# D3R900.net
KiCad netlist of a schematic drawn in Altium Designer
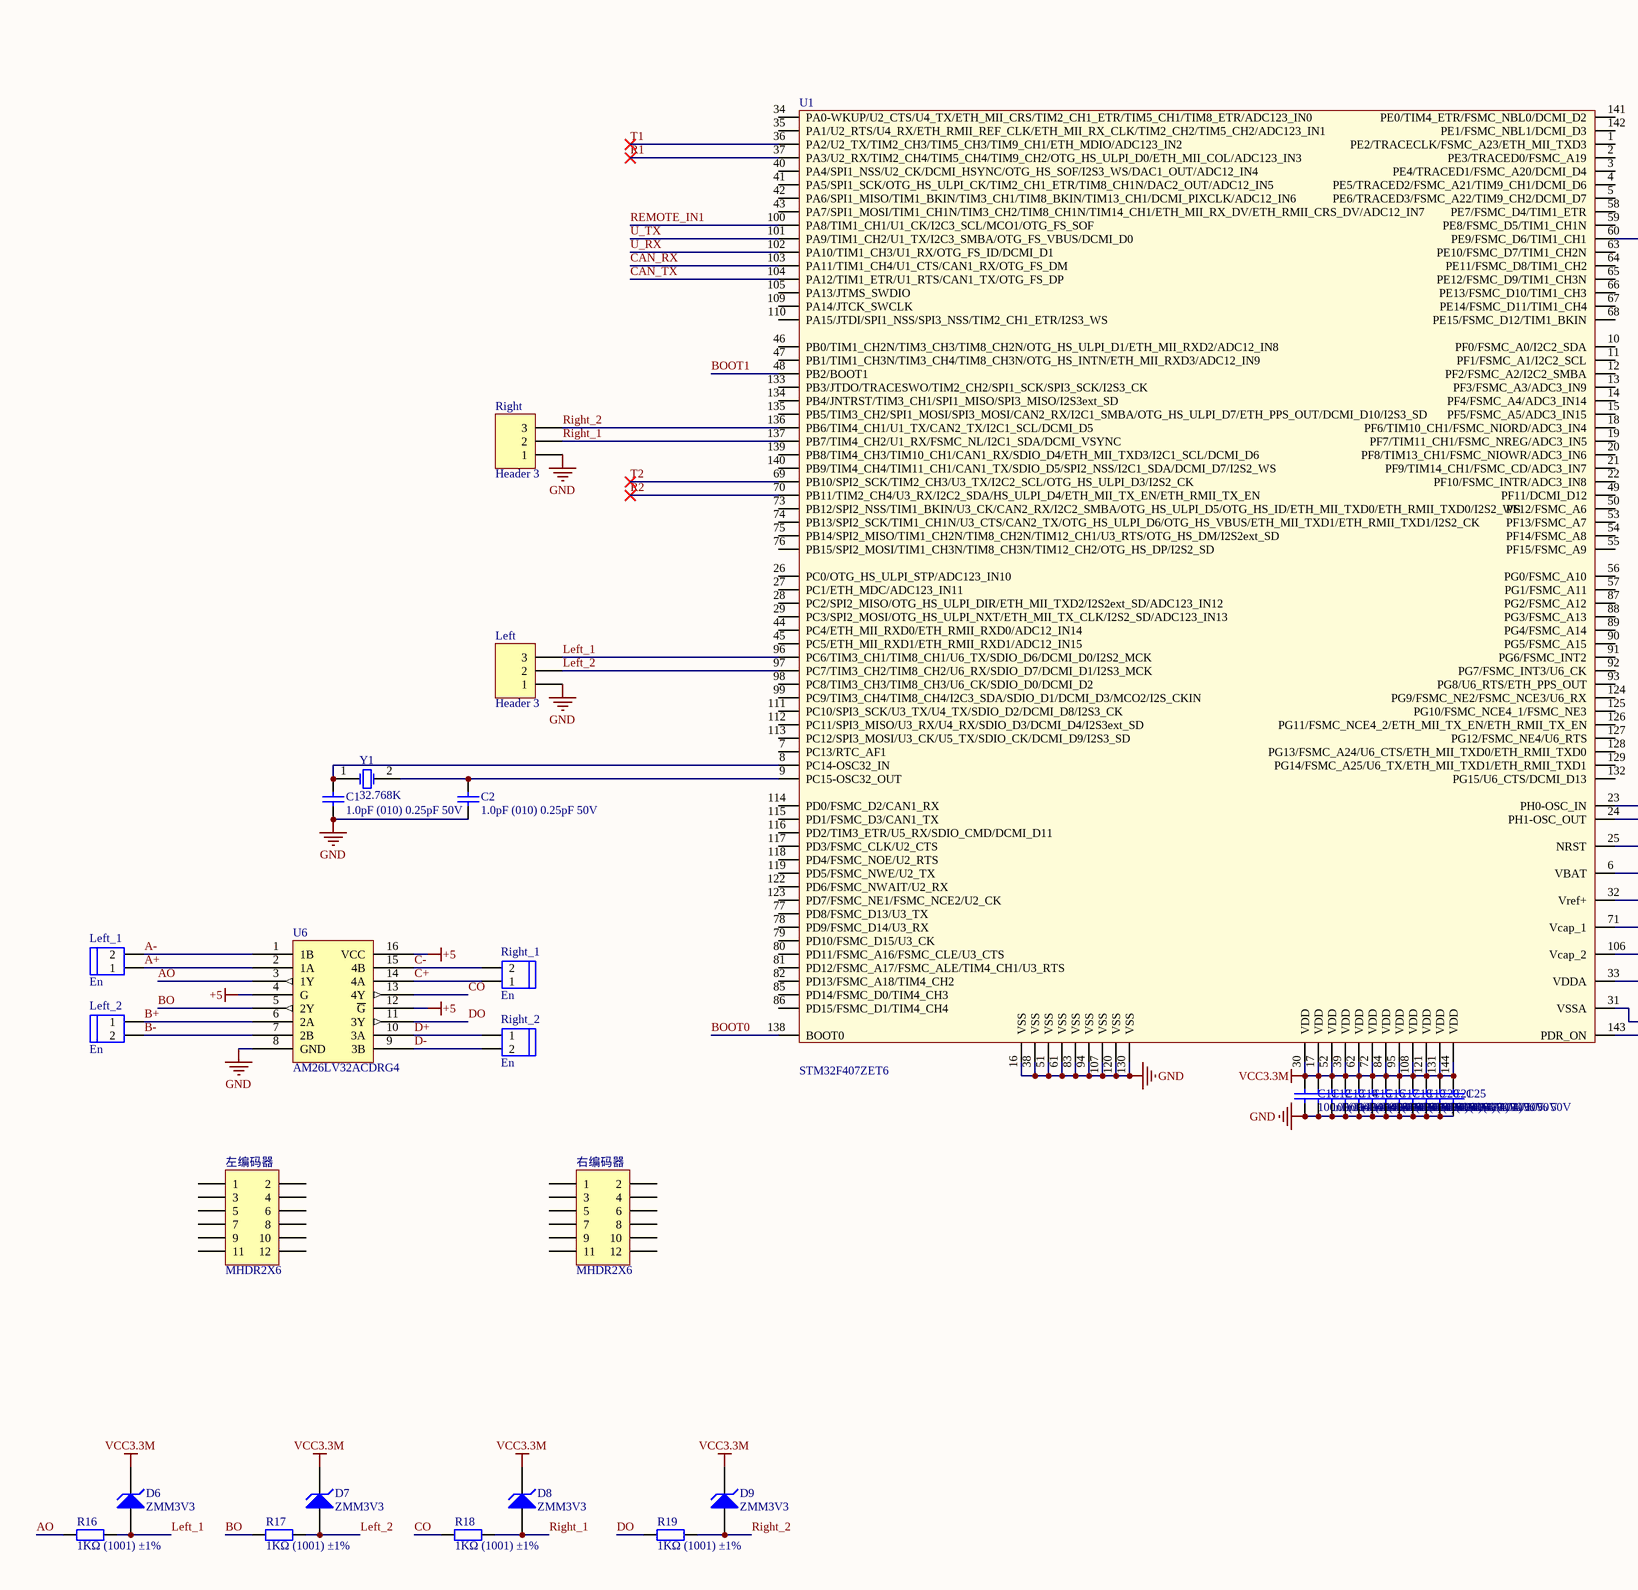
[diagram p0: D3R900.SchDoc, left]
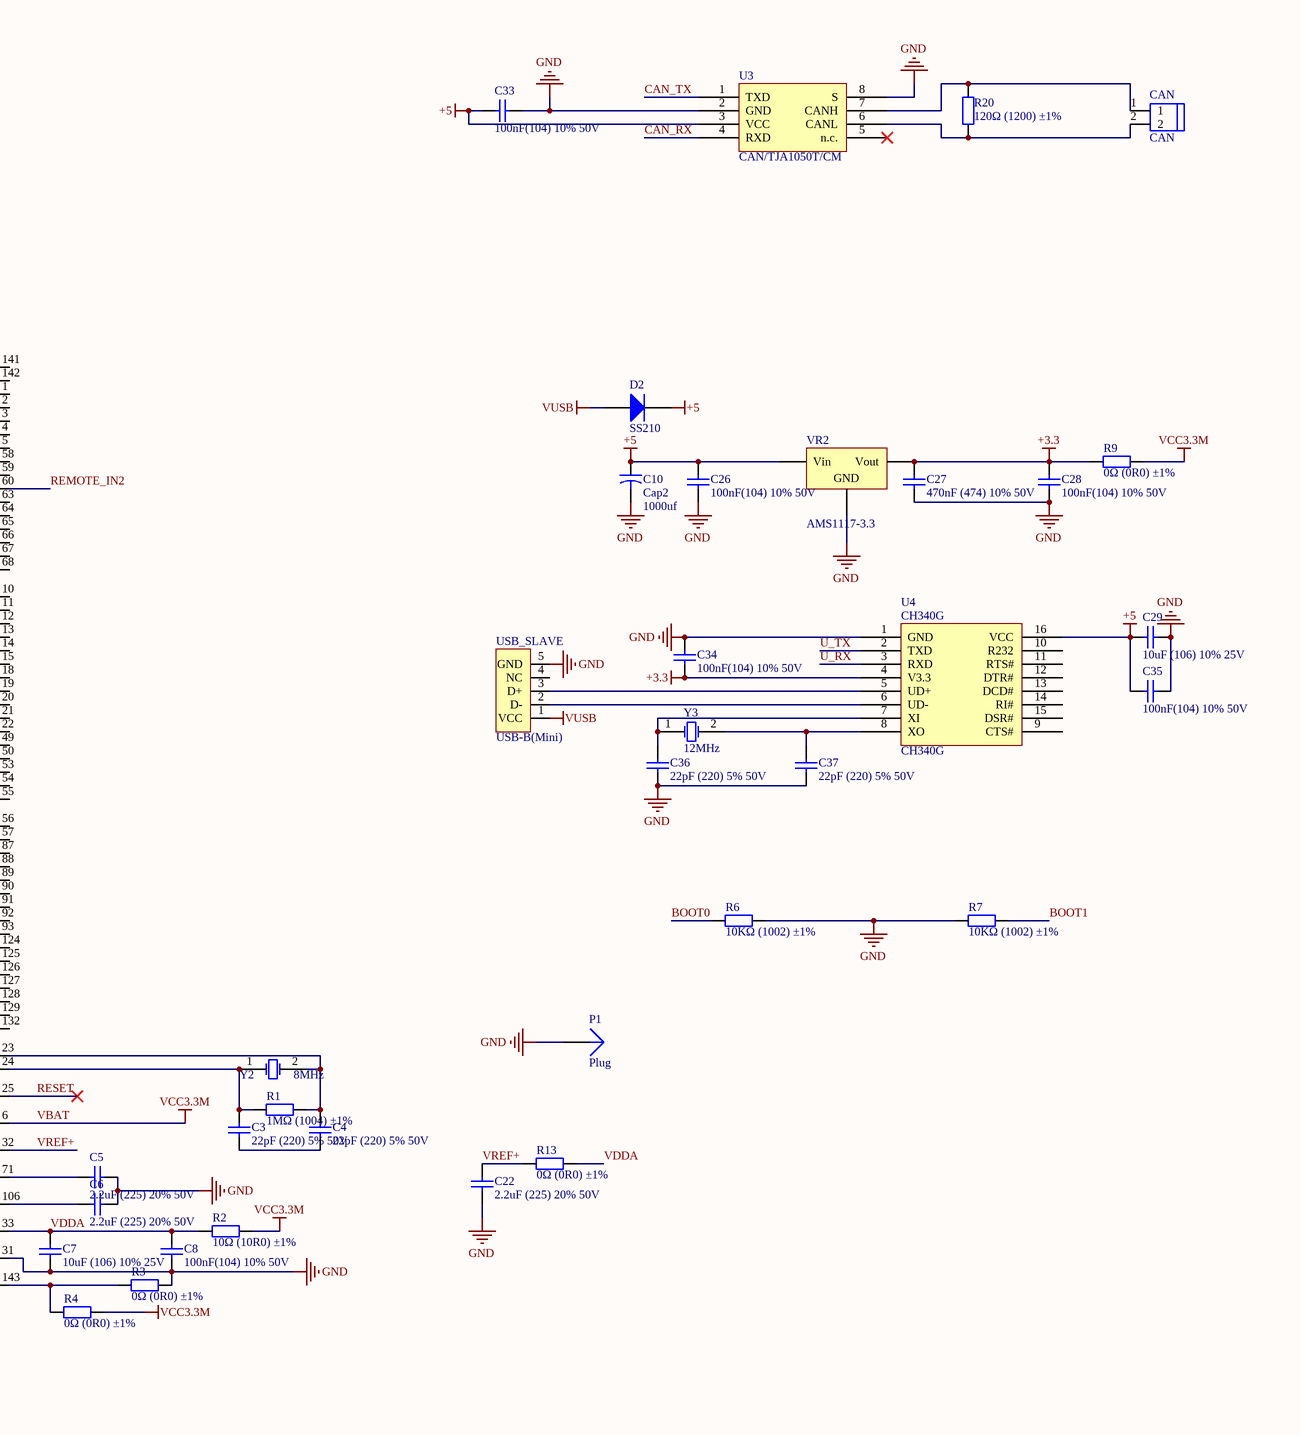
[diagram p1: D3R900.SchDoc, right]

(export (version "E")
  (design (tool "Eeschema 10.0.6"))
  (components
    (comp (ref "C1")
      (value "1.0pF (010) 0.25pF 50V")
      (footprint "LC-0805_C")
      (description "贴片电容")
      (libsource (lib "Miscellaneous Devices LC") (part "0805 1.0pF (010) 0.25pF 50V"))
    )
    (comp (ref "C2")
      (value "1.0pF (010) 0.25pF 50V")
      (footprint "LC-0805_C")
      (description "贴片电容")
      (libsource (lib "Miscellaneous Devices LC") (part "0805 1.0pF (010) 0.25pF 50V"))
    )
    (comp (ref "C3")
      (value "22pF (220) 5% 50V")
      (footprint "LC-0805_C")
      (description "贴片电容")
      (libsource (lib "Miscellaneous Devices LC") (part "0805 22pF (220) 5% 50V"))
    )
    (comp (ref "C4")
      (value "22pF (220) 5% 50V")
      (footprint "LC-0805_C")
      (description "贴片电容")
      (libsource (lib "Miscellaneous Devices LC") (part "0805 22pF (220) 5% 50V"))
    )
    (comp (ref "C5")
      (value "2.2uF (225) 20% 50V")
      (footprint "LC-0805_C")
      (description "贴片电容")
      (libsource (lib "Miscellaneous Devices LC") (part "0805 2.2uF (225) 20% 50V"))
    )
    (comp (ref "C6")
      (value "2.2uF (225) 20% 50V")
      (footprint "LC-0805_C")
      (description "贴片电容")
      (libsource (lib "Miscellaneous Devices LC") (part "0805 2.2uF (225) 20% 50V"))
    )
    (comp (ref "C7")
      (value "10uF (106) 10% 25V")
      (footprint "LC-0805_C")
      (description "贴片电容")
      (libsource (lib "Miscellaneous Devices LC") (part "0805 10uF (106) 10% 25V"))
    )
    (comp (ref "C8")
      (value "100nF(104) 10% 50V")
      (footprint "LC-0805_C")
      (description "贴片电容")
      (libsource (lib "Miscellaneous Devices LC") (part "0805 100nF(104) 10% 50V"))
    )
    (comp (ref "C10")
      (value "Cap2")
      (footprint "CAPR5-4X5")
      (description "Capacitor")
      (fields (field (name "ALTIUM_VALUE") "1000uf") (field (name "PUBLISHER") "Altium Limited"))
      (libsource (lib "Miscellaneous Devices") (part "Cap2"))
    )
    (comp (ref "C11")
      (value "100nF(104) 10% 50V")
      (footprint "LC-0805_C")
      (description "贴片电容")
      (libsource (lib "Miscellaneous Devices LC") (part "0805 100nF(104) 10% 50V"))
    )
    (comp (ref "C12")
      (value "100nF(104) 10% 50V")
      (footprint "LC-0805_C")
      (description "贴片电容")
      (libsource (lib "Miscellaneous Devices LC") (part "0805 100nF(104) 10% 50V"))
    )
    (comp (ref "C13")
      (value "100nF(104) 10% 50V")
      (footprint "LC-0805_C")
      (description "贴片电容")
      (libsource (lib "Miscellaneous Devices LC") (part "0805 100nF(104) 10% 50V"))
    )
    (comp (ref "C14")
      (value "100nF(104) 10% 50V")
      (footprint "LC-0805_C")
      (description "贴片电容")
      (libsource (lib "Miscellaneous Devices LC") (part "0805 100nF(104) 10% 50V"))
    )
    (comp (ref "C15")
      (value "100nF(104) 10% 50V")
      (footprint "LC-0805_C")
      (description "贴片电容")
      (libsource (lib "Miscellaneous Devices LC") (part "0805 100nF(104) 10% 50V"))
    )
    (comp (ref "C16")
      (value "100nF(104) 10% 50V")
      (footprint "LC-0805_C")
      (description "贴片电容")
      (libsource (lib "Miscellaneous Devices LC") (part "0805 100nF(104) 10% 50V"))
    )
    (comp (ref "C17")
      (value "100nF(104) 10% 50V")
      (footprint "LC-0805_C")
      (description "贴片电容")
      (libsource (lib "Miscellaneous Devices LC") (part "0805 100nF(104) 10% 50V"))
    )
    (comp (ref "C18")
      (value "100nF(104) 10% 50V")
      (footprint "LC-0805_C")
      (description "贴片电容")
      (libsource (lib "Miscellaneous Devices LC") (part "0805 100nF(104) 10% 50V"))
    )
    (comp (ref "C19")
      (value "100nF(104) 10% 50V")
      (footprint "LC-0805_C")
      (description "贴片电容")
      (libsource (lib "Miscellaneous Devices LC") (part "0805 100nF(104) 10% 50V"))
    )
    (comp (ref "C20")
      (value "100nF(104) 10% 50V")
      (footprint "LC-0805_C")
      (description "贴片电容")
      (libsource (lib "Miscellaneous Devices LC") (part "0805 100nF(104) 10% 50V"))
    )
    (comp (ref "C21")
      (value "100nF(104) 10% 50V")
      (footprint "LC-0805_C")
      (description "贴片电容")
      (libsource (lib "Miscellaneous Devices LC") (part "0805 100nF(104) 10% 50V"))
    )
    (comp (ref "C22")
      (value "2.2uF (225) 20% 50V")
      (footprint "LC-0805_C")
      (description "贴片电容")
      (libsource (lib "Miscellaneous Devices LC") (part "0805 2.2uF (225) 20% 50V"))
    )
    (comp (ref "C25")
      (value "100nF(104) 10% 50V")
      (footprint "LC-0805_C")
      (description "贴片电容")
      (libsource (lib "Miscellaneous Devices LC") (part "0805 100nF(104) 10% 50V"))
    )
    (comp (ref "C26")
      (value "100nF(104) 10% 50V")
      (footprint "LC-0805_C")
      (description "贴片电容")
      (libsource (lib "Miscellaneous Devices LC") (part "0805 100nF(104) 10% 50V"))
    )
    (comp (ref "C27")
      (value "470nF (474) 10% 50V")
      (footprint "LC-1206_C")
      (description "贴片电容")
      (libsource (lib "Miscellaneous Devices LC") (part "1206 470nF (474) 10% 50V"))
    )
    (comp (ref "C28")
      (value "100nF(104) 10% 50V")
      (footprint "LC-0805_C")
      (description "贴片电容")
      (libsource (lib "Miscellaneous Devices LC") (part "0805 100nF(104) 10% 50V"))
    )
    (comp (ref "C29")
      (value "10uF (106) 10% 25V")
      (footprint "LC-0805_C")
      (description "贴片电容")
      (libsource (lib "Miscellaneous Devices LC") (part "0805 10uF (106) 10% 25V"))
    )
    (comp (ref "C33")
      (value "100nF(104) 10% 50V")
      (footprint "LC-0805_C")
      (description "贴片电容")
      (libsource (lib "Miscellaneous Devices LC") (part "0805 100nF(104) 10% 50V"))
    )
    (comp (ref "C34")
      (value "100nF(104) 10% 50V")
      (footprint "LC-0805_C")
      (description "贴片电容")
      (libsource (lib "Miscellaneous Devices LC") (part "0805 100nF(104) 10% 50V"))
    )
    (comp (ref "C35")
      (value "100nF(104) 10% 50V")
      (footprint "LC-0805_C")
      (description "贴片电容")
      (libsource (lib "Miscellaneous Devices LC") (part "0805 100nF(104) 10% 50V"))
    )
    (comp (ref "C36")
      (value "22pF (220) 5% 50V")
      (footprint "LC-0805_C")
      (description "贴片电容")
      (libsource (lib "Miscellaneous Devices LC") (part "0805 22pF (220) 5% 50V"))
    )
    (comp (ref "C37")
      (value "22pF (220) 5% 50V")
      (footprint "LC-0805_C")
      (description "贴片电容")
      (libsource (lib "Miscellaneous Devices LC") (part "0805 22pF (220) 5% 50V"))
    )
    (comp (ref "CAN") (value "CAN") (footprint "HEAD2L-0.8") (libsource (lib "") (part "HEAD2_1")))
    (comp (ref "D2")
      (value "SS210")
      (footprint "LC-SMA(DO-214AC)_S1")
      (description "二极管")
      (libsource (lib "Miscellaneous Devices LC") (part "SMA(DO-214AC) SS210"))
    )
    (comp (ref "D6")
      (value "ZMM3V3")
      (footprint "LC-LL-34")
      (description "稳压二极管")
      (libsource (lib "Miscellaneous Devices LC") (part "LL-34 ZMM3V3"))
    )
    (comp (ref "D7")
      (value "ZMM3V3")
      (footprint "LC-LL-34")
      (description "稳压二极管")
      (libsource (lib "Miscellaneous Devices LC") (part "LL-34 ZMM3V3"))
    )
    (comp (ref "D8")
      (value "ZMM3V3")
      (footprint "LC-LL-34")
      (description "稳压二极管")
      (libsource (lib "Miscellaneous Devices LC") (part "LL-34 ZMM3V3"))
    )
    (comp (ref "D9")
      (value "ZMM3V3")
      (footprint "LC-LL-34")
      (description "稳压二极管")
      (libsource (lib "Miscellaneous Devices LC") (part "LL-34 ZMM3V3"))
    )
    (comp (ref "Left")
      (value "Header 3")
      (footprint "HDR1X3")
      (description "Header, 3-Pin")
      (fields (field (name "PUBLISHER") "Altium Limited"))
      (libsource (lib "Miscellaneous Connectors") (part "Header 3"))
    )
    (comp (ref "Left_1")
      (value "En")
      (footprint "HEAD2L-0.8")
      (libsource (lib "Explorer STM32F407封装库") (part "HEAD2"))
    )
    (comp (ref "Left_2")
      (value "En")
      (footprint "HEAD2L-0.8")
      (libsource (lib "Explorer STM32F407封装库") (part "HEAD2"))
    )
    (comp (ref "P1")
      (value "Plug")
      (footprint "PIN1")
      (fields (field (name "PUBLISHER") "Altium Limited"))
      (libsource (lib "Miscellaneous Connectors") (part "Plug"))
    )
    (comp (ref "R1")
      (value "1MΩ (1004) ±1%")
      (footprint "LC-0805_R")
      (description "贴片电阻")
      (libsource (lib "Miscellaneous Devices LC") (part "0805 1MΩ (1004) 1%"))
    )
    (comp (ref "R2")
      (value "10Ω (10R0) ±1%")
      (footprint "LC-0805_R")
      (description "贴片电阻")
      (libsource (lib "Miscellaneous Devices LC") (part "0805 10Ω (10R0) 1%"))
    )
    (comp (ref "R3")
      (value "0Ω (0R0) ±1%")
      (footprint "LC-0603_R")
      (description "贴片电阻")
      (libsource (lib "Miscellaneous Devices LC") (part "0603 0Ω (0R0) 1%"))
    )
    (comp (ref "R4")
      (value "0Ω (0R0) ±1%")
      (footprint "LC-0603_R")
      (description "贴片电阻")
      (libsource (lib "Miscellaneous Devices LC") (part "0603 0Ω (0R0) 1%"))
    )
    (comp (ref "R6")
      (value "10KΩ (1002) ±1%")
      (footprint "LC-0805_R")
      (description "贴片电阻")
      (libsource (lib "Miscellaneous Devices LC") (part "0805 10KΩ (1002) 1%"))
    )
    (comp (ref "R7")
      (value "10KΩ (1002) ±1%")
      (footprint "LC-0805_R")
      (description "贴片电阻")
      (libsource (lib "Miscellaneous Devices LC") (part "0805 10KΩ (1002) 1%"))
    )
    (comp (ref "R9")
      (value "0Ω (0R0) ±1%")
      (footprint "LC-0603_R")
      (description "贴片电阻")
      (libsource (lib "Miscellaneous Devices LC") (part "0603 0Ω (0R0) 1%"))
    )
    (comp (ref "R13")
      (value "0Ω (0R0) ±1%")
      (footprint "LC-0603_R")
      (description "贴片电阻")
      (libsource (lib "Miscellaneous Devices LC") (part "0603 0Ω (0R0) 1%"))
    )
    (comp (ref "R16")
      (value "1KΩ (1001) ±1%")
      (footprint "LC-0805_R")
      (description "贴片电阻")
      (libsource (lib "Miscellaneous Devices LC") (part "0805 1KΩ (1001) 1%"))
    )
    (comp (ref "R17")
      (value "1KΩ (1001) ±1%")
      (footprint "LC-0805_R")
      (description "贴片电阻")
      (libsource (lib "Miscellaneous Devices LC") (part "0805 1KΩ (1001) 1%"))
    )
    (comp (ref "R18")
      (value "1KΩ (1001) ±1%")
      (footprint "LC-0805_R")
      (description "贴片电阻")
      (libsource (lib "Miscellaneous Devices LC") (part "0805 1KΩ (1001) 1%"))
    )
    (comp (ref "R19")
      (value "1KΩ (1001) ±1%")
      (footprint "LC-0805_R")
      (description "贴片电阻")
      (libsource (lib "Miscellaneous Devices LC") (part "0805 1KΩ (1001) 1%"))
    )
    (comp (ref "R20")
      (value "120Ω (1200) ±1%")
      (footprint "LC-0805_R")
      (description "贴片电阻")
      (libsource (lib "Miscellaneous Devices LC") (part "0805 120Ω (1200) 1%"))
    )
    (comp (ref "Right")
      (value "Header 3")
      (footprint "HDR1X3")
      (description "Header, 3-Pin")
      (fields (field (name "PUBLISHER") "Altium Limited"))
      (libsource (lib "Miscellaneous Connectors") (part "Header 3"))
    )
    (comp (ref "Right_1")
      (value "En")
      (footprint "HEAD2L-0.8")
      (libsource (lib "Explorer STM32F407封装库") (part "HEAD2"))
    )
    (comp (ref "Right_2")
      (value "En")
      (footprint "HEAD2L-0.8")
      (libsource (lib "Explorer STM32F407封装库") (part "HEAD2"))
    )
    (comp (ref "U1")
      (value "STM32F407ZET6")
      (footprint "LQFP144")
      (libsource (lib "Explorer STM32F407封装库") (part "STM32F407ZET6"))
    )
    (comp (ref "U3")
      (value "CAN/TJA1050T/CM")
      (footprint "LC-SOIC-8_150mil")
      (description "CAN")
      (libsource (lib "Miscellaneous Devices LC") (part "CAN/TJA1050T/CM"))
    )
    (comp (ref "U4")
      (value "CH340G")
      (footprint "LC-SOIC-16_150mil")
      (description "USB")
      (libsource (lib "Miscellaneous Devices LC") (part "CH340G"))
    )
    (comp (ref "U6")
      (value "AM26LV32ACDRG4")
      (footprint "LC-SOIC-16_150mil")
      (description "接口芯片")
      (libsource (lib "Miscellaneous Devices LC") (part "AM26LS32ACDRG4"))
    )
    (comp (ref "USB_SLAVE")
      (value "USB-B(Mini)")
      (footprint "USB/SM0.8-6H5")
      (libsource (lib "Explorer STM32F407封装库") (part "USB5"))
    )
    (comp (ref "VR2")
      (value "AMS1117-3.3")
      (footprint "LC-SOT-223")
      (description "低压差线性稳压(LDO)")
      (libsource (lib "Miscellaneous Devices LC") (part "SOT-223 AMS1117-3.3"))
    )
    (comp (ref "Y1")
      (value "32.768K")
      (footprint "R38")
      (description "Crystal Oscillator")
      (fields (field (name "PUBLISHER") "Altium Limited"))
      (libsource (lib "Miscellaneous Devices") (part "XTAL"))
    )
    (comp (ref "Y2")
      (value "8MHz")
      (footprint "XTAL_US")
      (description "Crystal Oscillator")
      (fields (field (name "PUBLISHER") "Altium Limited"))
      (libsource (lib "Explorer STM32F407封装库") (part "XTAL"))
    )
    (comp (ref "Y3")
      (value "12MHz")
      (footprint "XTAL_US")
      (description "Crystal Oscillator")
      (fields (field (name "PUBLISHER") "Altium Limited"))
      (libsource (lib "Explorer STM32F407封装库") (part "XTAL"))
    )
    (comp (ref "右编码器")
      (value "MHDR2X6")
      (footprint "MHDR2X6")
      (description "Header, 6-Pin, Dual row")
      (fields (field (name "PUBLISHER") "Altium Limited"))
      (libsource (lib "Miscellaneous Connectors") (part "MHDR2X6"))
    )
    (comp (ref "左编码器")
      (value "MHDR2X6")
      (footprint "MHDR2X6")
      (description "Header, 6-Pin, Dual row")
      (fields (field (name "PUBLISHER") "Altium Limited"))
      (libsource (lib "Miscellaneous Connectors") (part "MHDR2X6"))
    )
  )
  (nets
    (net (code "1") (name "+3.3") (class "Default")
      (node (ref "C27") (pin "2") (pinfunction "2_2") (pintype "passive"))
      (node (ref "C28") (pin "2") (pinfunction "2_2") (pintype "passive"))
      (node (ref "C34") (pin "1") (pinfunction "1_1") (pintype "passive"))
      (node (ref "R9") (pin "1") (pinfunction "1_1") (pintype "passive"))
      (node (ref "U4") (pin "4") (pinfunction "V3.3_4") (pintype "passive"))
      (node (ref "VR2") (pin "2") (pinfunction "Vout_2") (pintype "passive"))
    )
    (net (code "2") (name "+5") (class "Default")
      (node (ref "C10") (pin "1") (pinfunction "1_1") (pintype "passive"))
      (node (ref "C26") (pin "2") (pinfunction "2_2") (pintype "passive"))
      (node (ref "C29") (pin "1") (pinfunction "1_1") (pintype "passive"))
      (node (ref "C33") (pin "1") (pinfunction "1_1") (pintype "passive"))
      (node (ref "C35") (pin "1") (pinfunction "1_1") (pintype "passive"))
      (node (ref "D2") (pin "2") (pinfunction "K_2") (pintype "passive"))
      (node (ref "U3") (pin "3") (pinfunction "VCC_3") (pintype "passive"))
      (node (ref "U4") (pin "16") (pinfunction "VCC_16") (pintype "passive"))
      (node (ref "U6") (pin "12") (pinfunction "~{G}_12") (pintype "passive"))
      (node (ref "U6") (pin "16") (pinfunction "VCC_16") (pintype "passive"))
      (node (ref "U6") (pin "4") (pinfunction "G_4") (pintype "passive"))
      (node (ref "VR2") (pin "3") (pinfunction "Vin_3") (pintype "passive"))
    )
    (net (code "3") (name "/A+") (class "Default")
      (node (ref "Left_1") (pin "1") (pinfunction "1_1") (pintype "passive"))
      (node (ref "U6") (pin "2") (pinfunction "1A_2") (pintype "passive"))
    )
    (net (code "4") (name "/A-") (class "Default")
      (node (ref "Left_1") (pin "2") (pinfunction "2_2") (pintype "passive"))
      (node (ref "U6") (pin "1") (pinfunction "1B_1") (pintype "passive"))
    )
    (net (code "5") (name "/AO") (class "Default")
      (node (ref "R16") (pin "1") (pinfunction "1_1") (pintype "passive"))
      (node (ref "U6") (pin "3") (pinfunction "1Y_3") (pintype "output"))
    )
    (net (code "6") (name "/B+") (class "Default")
      (node (ref "Left_2") (pin "1") (pinfunction "1_1") (pintype "passive"))
      (node (ref "U6") (pin "6") (pinfunction "2A_6") (pintype "passive"))
    )
    (net (code "7") (name "/B-") (class "Default")
      (node (ref "Left_2") (pin "2") (pinfunction "2_2") (pintype "passive"))
      (node (ref "U6") (pin "7") (pinfunction "2B_7") (pintype "passive"))
    )
    (net (code "8") (name "/BO") (class "Default")
      (node (ref "R17") (pin "1") (pinfunction "1_1") (pintype "passive"))
      (node (ref "U6") (pin "5") (pinfunction "2Y_5") (pintype "output"))
    )
    (net (code "9") (name "/BOOT0") (class "Default")
      (node (ref "R6") (pin "1") (pinfunction "1_1") (pintype "passive"))
      (node (ref "U1") (pin "138") (pinfunction "BOOT0_138") (pintype "passive"))
    )
    (net (code "10") (name "/BOOT1") (class "Default")
      (node (ref "R7") (pin "2") (pinfunction "2_2") (pintype "passive"))
      (node (ref "U1") (pin "48") (pinfunction "PB2/BOOT1_48") (pintype "passive"))
    )
    (net (code "11") (name "/C+") (class "Default")
      (node (ref "Right_1") (pin "1") (pinfunction "1_1") (pintype "passive"))
      (node (ref "U6") (pin "14") (pinfunction "4A_14") (pintype "passive"))
    )
    (net (code "12") (name "/C-") (class "Default")
      (node (ref "Right_1") (pin "2") (pinfunction "2_2") (pintype "passive"))
      (node (ref "U6") (pin "15") (pinfunction "4B_15") (pintype "passive"))
    )
    (net (code "13") (name "/CAN_RX") (class "Default")
      (node (ref "U1") (pin "103") (pinfunction "PA11/TIM1_CH4/U1_CTS/CAN1_RX/OTG_FS_DM_103") (pintype "passive"))
      (node (ref "U3") (pin "4") (pinfunction "RXD_4") (pintype "passive"))
    )
    (net (code "14") (name "/CAN_TX") (class "Default")
      (node (ref "U1") (pin "104") (pinfunction "PA12/TIM1_ETR/U1_RTS/CAN1_TX/OTG_FS_DP_104") (pintype "passive"))
      (node (ref "U3") (pin "1") (pinfunction "TXD_1") (pintype "passive"))
    )
    (net (code "15") (name "/CO") (class "Default")
      (node (ref "R18") (pin "1") (pinfunction "1_1") (pintype "passive"))
      (node (ref "U6") (pin "13") (pinfunction "4Y_13") (pintype "output"))
    )
    (net (code "16") (name "/D+") (class "Default")
      (node (ref "Right_2") (pin "1") (pinfunction "1_1") (pintype "passive"))
      (node (ref "U6") (pin "10") (pinfunction "3A_10") (pintype "passive"))
    )
    (net (code "17") (name "/D-") (class "Default")
      (node (ref "Right_2") (pin "2") (pinfunction "2_2") (pintype "passive"))
      (node (ref "U6") (pin "9") (pinfunction "3B_9") (pintype "passive"))
    )
    (net (code "18") (name "/DO") (class "Default")
      (node (ref "R19") (pin "1") (pinfunction "1_1") (pintype "passive"))
      (node (ref "U6") (pin "11") (pinfunction "3Y_11") (pintype "output"))
    )
    (net (code "19") (name "/Left_1") (class "Default")
      (node (ref "D6") (pin "1") (pinfunction "A_1") (pintype "passive"))
      (node (ref "Left") (pin "3") (pinfunction "3_3") (pintype "passive"))
      (node (ref "R16") (pin "2") (pinfunction "2_2") (pintype "passive"))
      (node (ref "U1") (pin "96") (pinfunction "PC6/TIM3_CH1/TIM8_CH1/U6_TX/SDIO_D6/DCMI_D0/I2S2_MCK_96") (pintype "passive"))
    )
    (net (code "20") (name "/Left_2") (class "Default")
      (node (ref "D7") (pin "1") (pinfunction "A_1") (pintype "passive"))
      (node (ref "Left") (pin "2") (pinfunction "2_2") (pintype "passive"))
      (node (ref "R17") (pin "2") (pinfunction "2_2") (pintype "passive"))
      (node (ref "U1") (pin "97") (pinfunction "PC7/TIM3_CH2/TIM8_CH2/U6_RX/SDIO_D7/DCMI_D1/I2S3_MCK_97") (pintype "passive"))
    )
    (net (code "21") (name "/R1") (class "Default")
      (node (ref "U1") (pin "37") (pinfunction "PA3/U2_RX/TIM2_CH4/TIM5_CH4/TIM9_CH2/OTG_HS_ULPI_D0/ETH_MII_COL/ADC123_IN3_37") (pintype "passive+no_connect"))
    )
    (net (code "22") (name "/R2") (class "Default")
      (node (ref "U1") (pin "70") (pinfunction "PB11/TIM2_CH4/U3_RX/I2C2_SDA/HS_ULPI_D4/ETH_MII_TX_EN/ETH_RMII_TX_EN_70") (pintype "passive+no_connect"))
    )
    (net (code "23") (name "/REMOTE_IN1") (class "Default")
      (node (ref "U1") (pin "100") (pinfunction "PA8/TIM1_CH1/U1_CK/I2C3_SCL/MCO1/OTG_FS_SOF_100") (pintype "passive"))
    )
    (net (code "24") (name "/REMOTE_IN2") (class "Default")
      (node (ref "U1") (pin "60") (pinfunction "PE9/FSMC_D6/TIM1_CH1_60") (pintype "passive"))
    )
    (net (code "25") (name "/RESET") (class "Default")
      (node (ref "U1") (pin "25") (pinfunction "NRST_25") (pintype "passive+no_connect"))
    )
    (net (code "26") (name "/Right_1") (class "Default")
      (node (ref "D8") (pin "1") (pinfunction "A_1") (pintype "passive"))
      (node (ref "R18") (pin "2") (pinfunction "2_2") (pintype "passive"))
      (node (ref "Right") (pin "2") (pinfunction "2_2") (pintype "passive"))
      (node (ref "U1") (pin "137") (pinfunction "PB7/TIM4_CH2/U1_RX/FSMC_NL/I2C1_SDA/DCMI_VSYNC_137") (pintype "passive"))
    )
    (net (code "27") (name "/Right_2") (class "Default")
      (node (ref "D9") (pin "1") (pinfunction "A_1") (pintype "passive"))
      (node (ref "R19") (pin "2") (pinfunction "2_2") (pintype "passive"))
      (node (ref "Right") (pin "3") (pinfunction "3_3") (pintype "passive"))
      (node (ref "U1") (pin "136") (pinfunction "PB6/TIM4_CH1/U1_TX/CAN2_TX/I2C1_SCL/DCMI_D5_136") (pintype "passive"))
    )
    (net (code "28") (name "/T1") (class "Default")
      (node (ref "U1") (pin "36") (pinfunction "PA2/U2_TX/TIM2_CH3/TIM5_CH3/TIM9_CH1/ETH_MDIO/ADC123_IN2_36") (pintype "passive+no_connect"))
    )
    (net (code "29") (name "/T2") (class "Default")
      (node (ref "U1") (pin "69") (pinfunction "PB10/SPI2_SCK/TIM2_CH3/U3_TX/I2C2_SCL/OTG_HS_ULPI_D3/I2S2_CK_69") (pintype "passive+no_connect"))
    )
    (net (code "30") (name "/U_RX") (class "Default")
      (node (ref "U1") (pin "102") (pinfunction "PA10/TIM1_CH3/U1_RX/OTG_FS_ID/DCMI_D1_102") (pintype "passive"))
      (node (ref "U4") (pin "3") (pinfunction "RXD_3") (pintype "passive"))
    )
    (net (code "31") (name "/U_TX") (class "Default")
      (node (ref "U1") (pin "101") (pinfunction "PA9/TIM1_CH2/U1_TX/I2C3_SMBA/OTG_FS_VBUS/DCMI_D0_101") (pintype "passive"))
      (node (ref "U4") (pin "2") (pinfunction "TXD_2") (pintype "passive"))
    )
    (net (code "32") (name "/VDDA") (class "Default")
      (node (ref "C7") (pin "2") (pinfunction "2_2") (pintype "passive"))
      (node (ref "C8") (pin "2") (pinfunction "2_2") (pintype "passive"))
      (node (ref "R13") (pin "2") (pinfunction "2_2") (pintype "passive"))
      (node (ref "R2") (pin "1") (pinfunction "1_1") (pintype "passive"))
      (node (ref "U1") (pin "33") (pinfunction "VDDA_33") (pintype "passive"))
    )
    (net (code "33") (name "/VREF+") (class "Default")
      (node (ref "C22") (pin "2") (pinfunction "2_2") (pintype "passive"))
      (node (ref "R13") (pin "1") (pinfunction "1_1") (pintype "passive"))
      (node (ref "U1") (pin "32") (pinfunction "Vref+_32") (pintype "passive"))
    )
    (net (code "34") (name "GND") (class "Default")
      (node (ref "C1") (pin "1") (pinfunction "1_1") (pintype "passive"))
      (node (ref "C10") (pin "2") (pinfunction "2_2") (pintype "passive"))
      (node (ref "C11") (pin "2") (pinfunction "2_2") (pintype "passive"))
      (node (ref "C12") (pin "2") (pinfunction "2_2") (pintype "passive"))
      (node (ref "C13") (pin "2") (pinfunction "2_2") (pintype "passive"))
      (node (ref "C14") (pin "2") (pinfunction "2_2") (pintype "passive"))
      (node (ref "C15") (pin "2") (pinfunction "2_2") (pintype "passive"))
      (node (ref "C16") (pin "2") (pinfunction "2_2") (pintype "passive"))
      (node (ref "C17") (pin "2") (pinfunction "2_2") (pintype "passive"))
      (node (ref "C18") (pin "2") (pinfunction "2_2") (pintype "passive"))
      (node (ref "C19") (pin "2") (pinfunction "2_2") (pintype "passive"))
      (node (ref "C2") (pin "1") (pinfunction "1_1") (pintype "passive"))
      (node (ref "C20") (pin "2") (pinfunction "2_2") (pintype "passive"))
      (node (ref "C21") (pin "2") (pinfunction "2_2") (pintype "passive"))
      (node (ref "C22") (pin "1") (pinfunction "1_1") (pintype "passive"))
      (node (ref "C25") (pin "2") (pinfunction "2_2") (pintype "passive"))
      (node (ref "C26") (pin "1") (pinfunction "1_1") (pintype "passive"))
      (node (ref "C27") (pin "1") (pinfunction "1_1") (pintype "passive"))
      (node (ref "C28") (pin "1") (pinfunction "1_1") (pintype "passive"))
      (node (ref "C29") (pin "2") (pinfunction "2_2") (pintype "passive"))
      (node (ref "C33") (pin "2") (pinfunction "2_2") (pintype "passive"))
      (node (ref "C34") (pin "2") (pinfunction "2_2") (pintype "passive"))
      (node (ref "C35") (pin "2") (pinfunction "2_2") (pintype "passive"))
      (node (ref "C36") (pin "1") (pinfunction "1_1") (pintype "passive"))
      (node (ref "C37") (pin "1") (pinfunction "1_1") (pintype "passive"))
      (node (ref "C5") (pin "2") (pinfunction "2_2") (pintype "passive"))
      (node (ref "C6") (pin "2") (pinfunction "2_2") (pintype "passive"))
      (node (ref "C7") (pin "1") (pinfunction "1_1") (pintype "passive"))
      (node (ref "C8") (pin "1") (pinfunction "1_1") (pintype "passive"))
      (node (ref "Left") (pin "1") (pinfunction "1_1") (pintype "passive"))
      (node (ref "P1") (pin "1") (pinfunction "1_1") (pintype "passive"))
      (node (ref "R3") (pin "2") (pinfunction "2_2") (pintype "passive"))
      (node (ref "R6") (pin "2") (pinfunction "2_2") (pintype "passive"))
      (node (ref "R7") (pin "1") (pinfunction "1_1") (pintype "passive"))
      (node (ref "Right") (pin "1") (pinfunction "1_1") (pintype "passive"))
      (node (ref "U1") (pin "107") (pinfunction "VSS_107") (pintype "passive"))
      (node (ref "U1") (pin "120") (pinfunction "VSS_120") (pintype "passive"))
      (node (ref "U1") (pin "130") (pinfunction "VSS_130") (pintype "passive"))
      (node (ref "U1") (pin "16") (pinfunction "VSS_16") (pintype "passive"))
      (node (ref "U1") (pin "31") (pinfunction "VSSA_31") (pintype "passive"))
      (node (ref "U1") (pin "38") (pinfunction "VSS_38") (pintype "passive"))
      (node (ref "U1") (pin "51") (pinfunction "VSS_51") (pintype "passive"))
      (node (ref "U1") (pin "61") (pinfunction "VSS_61") (pintype "passive"))
      (node (ref "U1") (pin "83") (pinfunction "VSS_83") (pintype "passive"))
      (node (ref "U1") (pin "94") (pinfunction "VSS_94") (pintype "passive"))
      (node (ref "U3") (pin "2") (pinfunction "GND_2") (pintype "passive"))
      (node (ref "U3") (pin "8") (pinfunction "S_8") (pintype "passive"))
      (node (ref "U4") (pin "1") (pinfunction "GND_1") (pintype "passive"))
      (node (ref "U6") (pin "8") (pinfunction "GND_8") (pintype "passive"))
      (node (ref "USB_SLAVE") (pin "5") (pinfunction "GND_5") (pintype "passive"))
      (node (ref "VR2") (pin "1") (pinfunction "GND_1") (pintype "passive"))
    )
    (net (code "35") (name "Net-(C3-Pad1)") (class "Default")
      (node (ref "C3") (pin "1") (pinfunction "1_1") (pintype "passive"))
      (node (ref "C4") (pin "1") (pinfunction "1_1") (pintype "passive"))
    )
    (net (code "36") (name "Net-(U1-PC14-OSC32_IN)") (class "Default")
      (node (ref "C1") (pin "2") (pinfunction "2_2") (pintype "passive"))
      (node (ref "U1") (pin "8") (pinfunction "PC14-OSC32_IN_8") (pintype "passive"))
      (node (ref "Y1") (pin "1") (pinfunction "OSC1_1") (pintype "passive"))
    )
    (net (code "37") (name "Net-(U1-PC15-OSC32_OUT)") (class "Default")
      (node (ref "C2") (pin "2") (pinfunction "2_2") (pintype "passive"))
      (node (ref "U1") (pin "9") (pinfunction "PC15-OSC32_OUT_9") (pintype "passive"))
      (node (ref "Y1") (pin "2") (pinfunction "OSC2_2") (pintype "passive"))
    )
    (net (code "38") (name "Net-(U1-PDR_ON)") (class "Default")
      (node (ref "R3") (pin "1") (pinfunction "1_1") (pintype "passive"))
      (node (ref "R4") (pin "1") (pinfunction "1_1") (pintype "passive"))
      (node (ref "U1") (pin "143") (pinfunction "PDR_ON_143") (pintype "passive"))
    )
    (net (code "39") (name "Net-(U1-PH0-OSC_IN)") (class "Default")
      (node (ref "C4") (pin "2") (pinfunction "2_2") (pintype "passive"))
      (node (ref "R1") (pin "2") (pinfunction "2_2") (pintype "passive"))
      (node (ref "U1") (pin "23") (pinfunction "PH0-OSC_IN_23") (pintype "passive"))
      (node (ref "Y2") (pin "2") (pinfunction "OSC2_2") (pintype "passive"))
    )
    (net (code "40") (name "Net-(U1-PH1-OSC_OUT)") (class "Default")
      (node (ref "C3") (pin "2") (pinfunction "2_2") (pintype "passive"))
      (node (ref "R1") (pin "1") (pinfunction "1_1") (pintype "passive"))
      (node (ref "U1") (pin "24") (pinfunction "PH1-OSC_OUT_24") (pintype "passive"))
      (node (ref "Y2") (pin "1") (pinfunction "OSC1_1") (pintype "passive"))
    )
    (net (code "41") (name "Net-(U1-Vcap_1)") (class "Default")
      (node (ref "C5") (pin "1") (pinfunction "1_1") (pintype "passive"))
      (node (ref "U1") (pin "71") (pinfunction "Vcap_1_71") (pintype "passive"))
    )
    (net (code "42") (name "Net-(U1-Vcap_2)") (class "Default")
      (node (ref "C6") (pin "1") (pinfunction "1_1") (pintype "passive"))
      (node (ref "U1") (pin "106") (pinfunction "Vcap_2_106") (pintype "passive"))
    )
    (net (code "43") (name "Net-(U3-CANH)") (class "Default")
      (node (ref "CAN") (pin "1") (pinfunction "1_1") (pintype "passive"))
      (node (ref "R20") (pin "2") (pinfunction "2_2") (pintype "passive"))
      (node (ref "U3") (pin "7") (pinfunction "CANH_7") (pintype "passive"))
    )
    (net (code "44") (name "Net-(U3-CANL)") (class "Default")
      (node (ref "CAN") (pin "2") (pinfunction "2_2") (pintype "passive"))
      (node (ref "R20") (pin "1") (pinfunction "1_1") (pintype "passive"))
      (node (ref "U3") (pin "6") (pinfunction "CANL_6") (pintype "passive"))
    )
    (net (code "45") (name "Net-(U4-UD+)") (class "Default")
      (node (ref "U4") (pin "5") (pinfunction "UD+_5") (pintype "passive"))
      (node (ref "USB_SLAVE") (pin "3") (pinfunction "D+_3") (pintype "passive"))
    )
    (net (code "46") (name "Net-(U4-UD-)") (class "Default")
      (node (ref "U4") (pin "6") (pinfunction "UD-_6") (pintype "passive"))
      (node (ref "USB_SLAVE") (pin "2") (pinfunction "D-_2") (pintype "passive"))
    )
    (net (code "47") (name "Net-(U4-XI)") (class "Default")
      (node (ref "C36") (pin "2") (pinfunction "2_2") (pintype "passive"))
      (node (ref "U4") (pin "7") (pinfunction "XI_7") (pintype "passive"))
      (node (ref "Y3") (pin "1") (pinfunction "OSC1_1") (pintype "passive"))
    )
    (net (code "48") (name "Net-(U4-XO)") (class "Default")
      (node (ref "C37") (pin "2") (pinfunction "2_2") (pintype "passive"))
      (node (ref "U4") (pin "8") (pinfunction "XO_8") (pintype "passive"))
      (node (ref "Y3") (pin "2") (pinfunction "OSC2_2") (pintype "passive"))
    )
    (net (code "49") (name "VCC3.3M") (class "Default")
      (node (ref "C11") (pin "1") (pinfunction "1_1") (pintype "passive"))
      (node (ref "C12") (pin "1") (pinfunction "1_1") (pintype "passive"))
      (node (ref "C13") (pin "1") (pinfunction "1_1") (pintype "passive"))
      (node (ref "C14") (pin "1") (pinfunction "1_1") (pintype "passive"))
      (node (ref "C15") (pin "1") (pinfunction "1_1") (pintype "passive"))
      (node (ref "C16") (pin "1") (pinfunction "1_1") (pintype "passive"))
      (node (ref "C17") (pin "1") (pinfunction "1_1") (pintype "passive"))
      (node (ref "C18") (pin "1") (pinfunction "1_1") (pintype "passive"))
      (node (ref "C19") (pin "1") (pinfunction "1_1") (pintype "passive"))
      (node (ref "C20") (pin "1") (pinfunction "1_1") (pintype "passive"))
      (node (ref "C21") (pin "1") (pinfunction "1_1") (pintype "passive"))
      (node (ref "C25") (pin "1") (pinfunction "1_1") (pintype "passive"))
      (node (ref "D6") (pin "2") (pinfunction "K_2") (pintype "passive"))
      (node (ref "D7") (pin "2") (pinfunction "K_2") (pintype "passive"))
      (node (ref "D8") (pin "2") (pinfunction "K_2") (pintype "passive"))
      (node (ref "D9") (pin "2") (pinfunction "K_2") (pintype "passive"))
      (node (ref "R2") (pin "2") (pinfunction "2_2") (pintype "passive"))
      (node (ref "R4") (pin "2") (pinfunction "2_2") (pintype "passive"))
      (node (ref "R9") (pin "2") (pinfunction "2_2") (pintype "passive"))
      (node (ref "U1") (pin "108") (pinfunction "VDD_108") (pintype "passive"))
      (node (ref "U1") (pin "121") (pinfunction "VDD_121") (pintype "passive"))
      (node (ref "U1") (pin "131") (pinfunction "VDD_131") (pintype "passive"))
      (node (ref "U1") (pin "144") (pinfunction "VDD_144") (pintype "passive"))
      (node (ref "U1") (pin "17") (pinfunction "VDD_17") (pintype "passive"))
      (node (ref "U1") (pin "30") (pinfunction "VDD_30") (pintype "passive"))
      (node (ref "U1") (pin "39") (pinfunction "VDD_39") (pintype "passive"))
      (node (ref "U1") (pin "52") (pinfunction "VDD_52") (pintype "passive"))
      (node (ref "U1") (pin "6") (pinfunction "VBAT_6") (pintype "passive"))
      (node (ref "U1") (pin "62") (pinfunction "VDD_62") (pintype "passive"))
      (node (ref "U1") (pin "72") (pinfunction "VDD_72") (pintype "passive"))
      (node (ref "U1") (pin "84") (pinfunction "VDD_84") (pintype "passive"))
      (node (ref "U1") (pin "95") (pinfunction "VDD_95") (pintype "passive"))
    )
    (net (code "50") (name "VUSB") (class "Default")
      (node (ref "D2") (pin "1") (pinfunction "A_1") (pintype "passive"))
      (node (ref "USB_SLAVE") (pin "1") (pinfunction "VCC_1") (pintype "passive"))
    )
    (net (code "51") (name "unconnected-(U1-PA0-WKUP{slash}U2_CTS{slash}U4_TX{slash}ETH_MII_CRS{slash}TIM2_CH1_ETR{slash}TIM5_CH1{slash}TIM8_ETR{slash}ADC123_IN0-Pad34)") (class "Default")
      (node (ref "U1") (pin "34") (pinfunction "PA0-WKUP/U2_CTS/U4_TX/ETH_MII_CRS/TIM2_CH1_ETR/TIM5_CH1/TIM8_ETR/ADC123_IN0_34") (pintype "passive"))
    )
    (net (code "52") (name "unconnected-(U1-PA1{slash}U2_RTS{slash}U4_RX{slash}ETH_RMII_REF_CLK{slash}ETH_MII_RX_CLK{slash}TIM2_CH2{slash}TIM5_CH2{slash}ADC123_IN1-Pad35)") (class "Default")
      (node (ref "U1") (pin "35") (pinfunction "PA1/U2_RTS/U4_RX/ETH_RMII_REF_CLK/ETH_MII_RX_CLK/TIM2_CH2/TIM5_CH2/ADC123_IN1_35") (pintype "passive"))
    )
    (net (code "53") (name "unconnected-(U1-PA4{slash}SPI1_NSS{slash}U2_CK{slash}DCMI_HSYNC{slash}OTG_HS_SOF{slash}I2S3_WS{slash}DAC1_OUT{slash}ADC12_IN4-Pad40)") (class "Default")
      (node (ref "U1") (pin "40") (pinfunction "PA4/SPI1_NSS/U2_CK/DCMI_HSYNC/OTG_HS_SOF/I2S3_WS/DAC1_OUT/ADC12_IN4_40") (pintype "passive"))
    )
    (net (code "54") (name "unconnected-(U1-PA5{slash}SPI1_SCK{slash}OTG_HS_ULPI_CK{slash}TIM2_CH1_ETR{slash}TIM8_CH1N{slash}DAC2_OUT{slash}ADC12_IN5-Pad41)") (class "Default")
      (node (ref "U1") (pin "41") (pinfunction "PA5/SPI1_SCK/OTG_HS_ULPI_CK/TIM2_CH1_ETR/TIM8_CH1N/DAC2_OUT/ADC12_IN5_41") (pintype "passive"))
    )
    (net (code "55") (name "unconnected-(U1-PA6{slash}SPI1_MISO{slash}TIM1_BKIN{slash}TIM3_CH1{slash}TIM8_BKIN{slash}TIM13_CH1{slash}DCMI_PIXCLK{slash}ADC12_IN6-Pad42)") (class "Default")
      (node (ref "U1") (pin "42") (pinfunction "PA6/SPI1_MISO/TIM1_BKIN/TIM3_CH1/TIM8_BKIN/TIM13_CH1/DCMI_PIXCLK/ADC12_IN6_42") (pintype "passive"))
    )
    (net (code "56") (name "unconnected-(U1-PA7{slash}SPI1_MOSI{slash}TIM1_CH1N{slash}TIM3_CH2{slash}TIM8_CH1N{slash}TIM14_CH1{slash}ETH_MII_RX_DV{slash}ETH_RMII_CRS_DV{slash}ADC12_IN7-Pad43)") (class "Default")
      (node (ref "U1") (pin "43") (pinfunction "PA7/SPI1_MOSI/TIM1_CH1N/TIM3_CH2/TIM8_CH1N/TIM14_CH1/ETH_MII_RX_DV/ETH_RMII_CRS_DV/ADC12_IN7_43") (pintype "passive"))
    )
    (net (code "57") (name "unconnected-(U1-PA13{slash}JTMS_SWDIO-Pad105)") (class "Default")
      (node (ref "U1") (pin "105") (pinfunction "PA13/JTMS_SWDIO_105") (pintype "passive"))
    )
    (net (code "58") (name "unconnected-(U1-PA14{slash}JTCK_SWCLK-Pad109)") (class "Default")
      (node (ref "U1") (pin "109") (pinfunction "PA14/JTCK_SWCLK_109") (pintype "passive"))
    )
    (net (code "59") (name "unconnected-(U1-PA15{slash}JTDI{slash}SPI1_NSS{slash}SPI3_NSS{slash}TIM2_CH1_ETR{slash}I2S3_WS-Pad110)") (class "Default")
      (node (ref "U1") (pin "110") (pinfunction "PA15/JTDI/SPI1_NSS/SPI3_NSS/TIM2_CH1_ETR/I2S3_WS_110") (pintype "passive"))
    )
    (net (code "60") (name "unconnected-(U1-PB0{slash}TIM1_CH2N{slash}TIM3_CH3{slash}TIM8_CH2N{slash}OTG_HS_ULPI_D1{slash}ETH_MII_RXD2{slash}ADC12_IN8-Pad46)") (class "Default")
      (node (ref "U1") (pin "46") (pinfunction "PB0/TIM1_CH2N/TIM3_CH3/TIM8_CH2N/OTG_HS_ULPI_D1/ETH_MII_RXD2/ADC12_IN8_46") (pintype "passive"))
    )
    (net (code "61") (name "unconnected-(U1-PB1{slash}TIM1_CH3N{slash}TIM3_CH4{slash}TIM8_CH3N{slash}OTG_HS_INTN{slash}ETH_MII_RXD3{slash}ADC12_IN9-Pad47)") (class "Default")
      (node (ref "U1") (pin "47") (pinfunction "PB1/TIM1_CH3N/TIM3_CH4/TIM8_CH3N/OTG_HS_INTN/ETH_MII_RXD3/ADC12_IN9_47") (pintype "passive"))
    )
    (net (code "62") (name "unconnected-(U1-PB3{slash}JTDO{slash}TRACESWO{slash}TIM2_CH2{slash}SPI1_SCK{slash}SPI3_SCK{slash}I2S3_CK-Pad133)") (class "Default")
      (node (ref "U1") (pin "133") (pinfunction "PB3/JTDO/TRACESWO/TIM2_CH2/SPI1_SCK/SPI3_SCK/I2S3_CK_133") (pintype "passive"))
    )
    (net (code "63") (name "unconnected-(U1-PB4{slash}JNTRST{slash}TIM3_CH1{slash}SPI1_MISO{slash}SPI3_MISO{slash}I2S3ext_SD-Pad134)") (class "Default")
      (node (ref "U1") (pin "134") (pinfunction "PB4/JNTRST/TIM3_CH1/SPI1_MISO/SPI3_MISO/I2S3ext_SD_134") (pintype "passive"))
    )
    (net (code "64") (name "unconnected-(U1-PB5{slash}TIM3_CH2{slash}SPI1_MOSI{slash}SPI3_MOSI{slash}CAN2_RX{slash}I2C1_SMBA{slash}OTG_HS_ULPI_D7{slash}ETH_PPS_OUT{slash}DCMI_D10{slash}I2S3_SD-Pad135)") (class "Default")
      (node (ref "U1") (pin "135") (pinfunction "PB5/TIM3_CH2/SPI1_MOSI/SPI3_MOSI/CAN2_RX/I2C1_SMBA/OTG_HS_ULPI_D7/ETH_PPS_OUT/DCMI_D10/I2S3_SD_135") (pintype "passive"))
    )
    (net (code "65") (name "unconnected-(U1-PB8{slash}TIM4_CH3{slash}TIM10_CH1{slash}CAN1_RX{slash}SDIO_D4{slash}ETH_MII_TXD3{slash}I2C1_SCL{slash}DCMI_D6-Pad139)") (class "Default")
      (node (ref "U1") (pin "139") (pinfunction "PB8/TIM4_CH3/TIM10_CH1/CAN1_RX/SDIO_D4/ETH_MII_TXD3/I2C1_SCL/DCMI_D6_139") (pintype "passive"))
    )
    (net (code "66") (name "unconnected-(U1-PB9{slash}TIM4_CH4{slash}TIM11_CH1{slash}CAN1_TX{slash}SDIO_D5{slash}SPI2_NSS{slash}I2C1_SDA{slash}DCMI_D7{slash}I2S2_WS-Pad140)") (class "Default")
      (node (ref "U1") (pin "140") (pinfunction "PB9/TIM4_CH4/TIM11_CH1/CAN1_TX/SDIO_D5/SPI2_NSS/I2C1_SDA/DCMI_D7/I2S2_WS_140") (pintype "passive"))
    )
    (net (code "67") (name "unconnected-(U1-PB12{slash}SPI2_NSS{slash}TIM1_BKIN{slash}U3_CK{slash}CAN2_RX{slash}I2C2_SMBA{slash}OTG_HS_ULPI_D5{slash}OTG_HS_ID{slash}ETH_MII_TXD0{slash}ETH_RMII_TXD0{slash}I2S2_WS-Pad73)") (class "Default")
      (node (ref "U1") (pin "73") (pinfunction "PB12/SPI2_NSS/TIM1_BKIN/U3_CK/CAN2_RX/I2C2_SMBA/OTG_HS_ULPI_D5/OTG_HS_ID/ETH_MII_TXD0/ETH_RMII_TXD0/I2S2_WS_73") (pintype "passive"))
    )
    (net (code "68") (name "unconnected-(U1-PB13{slash}SPI2_SCK{slash}TIM1_CH1N{slash}U3_CTS{slash}CAN2_TX{slash}OTG_HS_ULPI_D6{slash}OTG_HS_VBUS{slash}ETH_MII_TXD1{slash}ETH_RMII_TXD1{slash}I2S2_CK-Pad74)") (class "Default")
      (node (ref "U1") (pin "74") (pinfunction "PB13/SPI2_SCK/TIM1_CH1N/U3_CTS/CAN2_TX/OTG_HS_ULPI_D6/OTG_HS_VBUS/ETH_MII_TXD1/ETH_RMII_TXD1/I2S2_CK_74") (pintype "passive"))
    )
    (net (code "69") (name "unconnected-(U1-PB14{slash}SPI2_MISO{slash}TIM1_CH2N{slash}TIM8_CH2N{slash}TIM12_CH1{slash}U3_RTS{slash}OTG_HS_DM{slash}I2S2ext_SD-Pad75)") (class "Default")
      (node (ref "U1") (pin "75") (pinfunction "PB14/SPI2_MISO/TIM1_CH2N/TIM8_CH2N/TIM12_CH1/U3_RTS/OTG_HS_DM/I2S2ext_SD_75") (pintype "passive"))
    )
    (net (code "70") (name "unconnected-(U1-PB15{slash}SPI2_MOSI{slash}TIM1_CH3N{slash}TIM8_CH3N{slash}TIM12_CH2{slash}OTG_HS_DP{slash}I2S2_SD-Pad76)") (class "Default")
      (node (ref "U1") (pin "76") (pinfunction "PB15/SPI2_MOSI/TIM1_CH3N/TIM8_CH3N/TIM12_CH2/OTG_HS_DP/I2S2_SD_76") (pintype "passive"))
    )
    (net (code "71") (name "unconnected-(U1-PC0{slash}OTG_HS_ULPI_STP{slash}ADC123_IN10-Pad26)") (class "Default")
      (node (ref "U1") (pin "26") (pinfunction "PC0/OTG_HS_ULPI_STP/ADC123_IN10_26") (pintype "passive"))
    )
    (net (code "72") (name "unconnected-(U1-PC1{slash}ETH_MDC{slash}ADC123_IN11-Pad27)") (class "Default")
      (node (ref "U1") (pin "27") (pinfunction "PC1/ETH_MDC/ADC123_IN11_27") (pintype "passive"))
    )
    (net (code "73") (name "unconnected-(U1-PC2{slash}SPI2_MISO{slash}OTG_HS_ULPI_DIR{slash}ETH_MII_TXD2{slash}I2S2ext_SD{slash}ADC123_IN12-Pad28)") (class "Default")
      (node (ref "U1") (pin "28") (pinfunction "PC2/SPI2_MISO/OTG_HS_ULPI_DIR/ETH_MII_TXD2/I2S2ext_SD/ADC123_IN12_28") (pintype "passive"))
    )
    (net (code "74") (name "unconnected-(U1-PC3{slash}SPI2_MOSI{slash}OTG_HS_ULPI_NXT{slash}ETH_MII_TX_CLK{slash}I2S2_SD{slash}ADC123_IN13-Pad29)") (class "Default")
      (node (ref "U1") (pin "29") (pinfunction "PC3/SPI2_MOSI/OTG_HS_ULPI_NXT/ETH_MII_TX_CLK/I2S2_SD/ADC123_IN13_29") (pintype "passive"))
    )
    (net (code "75") (name "unconnected-(U1-PC4{slash}ETH_MII_RXD0{slash}ETH_RMII_RXD0{slash}ADC12_IN14-Pad44)") (class "Default")
      (node (ref "U1") (pin "44") (pinfunction "PC4/ETH_MII_RXD0/ETH_RMII_RXD0/ADC12_IN14_44") (pintype "passive"))
    )
    (net (code "76") (name "unconnected-(U1-PC5{slash}ETH_MII_RXD1{slash}ETH_RMII_RXD1{slash}ADC12_IN15-Pad45)") (class "Default")
      (node (ref "U1") (pin "45") (pinfunction "PC5/ETH_MII_RXD1/ETH_RMII_RXD1/ADC12_IN15_45") (pintype "passive"))
    )
    (net (code "77") (name "unconnected-(U1-PC8{slash}TIM3_CH3{slash}TIM8_CH3{slash}U6_CK{slash}SDIO_D0{slash}DCMI_D2-Pad98)") (class "Default")
      (node (ref "U1") (pin "98") (pinfunction "PC8/TIM3_CH3/TIM8_CH3/U6_CK/SDIO_D0/DCMI_D2_98") (pintype "passive"))
    )
    (net (code "78") (name "unconnected-(U1-PC9{slash}TIM3_CH4{slash}TIM8_CH4{slash}I2C3_SDA{slash}SDIO_D1{slash}DCMI_D3{slash}MCO2{slash}I2S_CKIN-Pad99)") (class "Default")
      (node (ref "U1") (pin "99") (pinfunction "PC9/TIM3_CH4/TIM8_CH4/I2C3_SDA/SDIO_D1/DCMI_D3/MCO2/I2S_CKIN_99") (pintype "passive"))
    )
    (net (code "79") (name "unconnected-(U1-PC10{slash}SPI3_SCK{slash}U3_TX{slash}U4_TX{slash}SDIO_D2{slash}DCMI_D8{slash}I2S3_CK-Pad111)") (class "Default")
      (node (ref "U1") (pin "111") (pinfunction "PC10/SPI3_SCK/U3_TX/U4_TX/SDIO_D2/DCMI_D8/I2S3_CK_111") (pintype "passive"))
    )
    (net (code "80") (name "unconnected-(U1-PC11{slash}SPI3_MISO{slash}U3_RX{slash}U4_RX{slash}SDIO_D3{slash}DCMI_D4{slash}I2S3ext_SD-Pad112)") (class "Default")
      (node (ref "U1") (pin "112") (pinfunction "PC11/SPI3_MISO/U3_RX/U4_RX/SDIO_D3/DCMI_D4/I2S3ext_SD_112") (pintype "passive"))
    )
    (net (code "81") (name "unconnected-(U1-PC12{slash}SPI3_MOSI{slash}U3_CK{slash}U5_TX{slash}SDIO_CK{slash}DCMI_D9{slash}I2S3_SD-Pad113)") (class "Default")
      (node (ref "U1") (pin "113") (pinfunction "PC12/SPI3_MOSI/U3_CK/U5_TX/SDIO_CK/DCMI_D9/I2S3_SD_113") (pintype "passive"))
    )
    (net (code "82") (name "unconnected-(U1-PC13{slash}RTC_AF1-Pad7)") (class "Default")
      (node (ref "U1") (pin "7") (pinfunction "PC13/RTC_AF1_7") (pintype "passive"))
    )
    (net (code "83") (name "unconnected-(U1-PD0{slash}FSMC_D2{slash}CAN1_RX-Pad114)") (class "Default")
      (node (ref "U1") (pin "114") (pinfunction "PD0/FSMC_D2/CAN1_RX_114") (pintype "passive"))
    )
    (net (code "84") (name "unconnected-(U1-PD1{slash}FSMC_D3{slash}CAN1_TX-Pad115)") (class "Default")
      (node (ref "U1") (pin "115") (pinfunction "PD1/FSMC_D3/CAN1_TX_115") (pintype "passive"))
    )
    (net (code "85") (name "unconnected-(U1-PD2{slash}TIM3_ETR{slash}U5_RX{slash}SDIO_CMD{slash}DCMI_D11-Pad116)") (class "Default")
      (node (ref "U1") (pin "116") (pinfunction "PD2/TIM3_ETR/U5_RX/SDIO_CMD/DCMI_D11_116") (pintype "passive"))
    )
    (net (code "86") (name "unconnected-(U1-PD3{slash}FSMC_CLK{slash}U2_CTS-Pad117)") (class "Default")
      (node (ref "U1") (pin "117") (pinfunction "PD3/FSMC_CLK/U2_CTS_117") (pintype "passive"))
    )
    (net (code "87") (name "unconnected-(U1-PD4{slash}FSMC_NOE{slash}U2_RTS-Pad118)") (class "Default")
      (node (ref "U1") (pin "118") (pinfunction "PD4/FSMC_NOE/U2_RTS_118") (pintype "passive"))
    )
    (net (code "88") (name "unconnected-(U1-PD5{slash}FSMC_NWE{slash}U2_TX-Pad119)") (class "Default")
      (node (ref "U1") (pin "119") (pinfunction "PD5/FSMC_NWE/U2_TX_119") (pintype "passive"))
    )
    (net (code "89") (name "unconnected-(U1-PD6{slash}FSMC_NWAIT{slash}U2_RX-Pad122)") (class "Default")
      (node (ref "U1") (pin "122") (pinfunction "PD6/FSMC_NWAIT/U2_RX_122") (pintype "passive"))
    )
    (net (code "90") (name "unconnected-(U1-PD7{slash}FSMC_NE1{slash}FSMC_NCE2{slash}U2_CK-Pad123)") (class "Default")
      (node (ref "U1") (pin "123") (pinfunction "PD7/FSMC_NE1/FSMC_NCE2/U2_CK_123") (pintype "passive"))
    )
    (net (code "91") (name "unconnected-(U1-PD8{slash}FSMC_D13{slash}U3_TX-Pad77)") (class "Default")
      (node (ref "U1") (pin "77") (pinfunction "PD8/FSMC_D13/U3_TX_77") (pintype "passive"))
    )
    (net (code "92") (name "unconnected-(U1-PD9{slash}FSMC_D14{slash}U3_RX-Pad78)") (class "Default")
      (node (ref "U1") (pin "78") (pinfunction "PD9/FSMC_D14/U3_RX_78") (pintype "passive"))
    )
    (net (code "93") (name "unconnected-(U1-PD10{slash}FSMC_D15{slash}U3_CK-Pad79)") (class "Default")
      (node (ref "U1") (pin "79") (pinfunction "PD10/FSMC_D15/U3_CK_79") (pintype "passive"))
    )
    (net (code "94") (name "unconnected-(U1-PD11{slash}FSMC_A16{slash}FSMC_CLE{slash}U3_CTS-Pad80)") (class "Default")
      (node (ref "U1") (pin "80") (pinfunction "PD11/FSMC_A16/FSMC_CLE/U3_CTS_80") (pintype "passive"))
    )
    (net (code "95") (name "unconnected-(U1-PD12{slash}FSMC_A17{slash}FSMC_ALE{slash}TIM4_CH1{slash}U3_RTS-Pad81)") (class "Default")
      (node (ref "U1") (pin "81") (pinfunction "PD12/FSMC_A17/FSMC_ALE/TIM4_CH1/U3_RTS_81") (pintype "passive"))
    )
    (net (code "96") (name "unconnected-(U1-PD13{slash}FSMC_A18{slash}TIM4_CH2-Pad82)") (class "Default")
      (node (ref "U1") (pin "82") (pinfunction "PD13/FSMC_A18/TIM4_CH2_82") (pintype "passive"))
    )
    (net (code "97") (name "unconnected-(U1-PD14{slash}FSMC_D0{slash}TIM4_CH3-Pad85)") (class "Default")
      (node (ref "U1") (pin "85") (pinfunction "PD14/FSMC_D0/TIM4_CH3_85") (pintype "passive"))
    )
    (net (code "98") (name "unconnected-(U1-PD15{slash}FSMC_D1{slash}TIM4_CH4-Pad86)") (class "Default")
      (node (ref "U1") (pin "86") (pinfunction "PD15/FSMC_D1/TIM4_CH4_86") (pintype "passive"))
    )
    (net (code "99") (name "unconnected-(U1-PE0{slash}TIM4_ETR{slash}FSMC_NBL0{slash}DCMI_D2-Pad141)") (class "Default")
      (node (ref "U1") (pin "141") (pinfunction "PE0/TIM4_ETR/FSMC_NBL0/DCMI_D2_141") (pintype "passive"))
    )
    (net (code "100") (name "unconnected-(U1-PE1{slash}FSMC_NBL1{slash}DCMI_D3-Pad142)") (class "Default")
      (node (ref "U1") (pin "142") (pinfunction "PE1/FSMC_NBL1/DCMI_D3_142") (pintype "passive"))
    )
    (net (code "101") (name "unconnected-(U1-PE2{slash}TRACECLK{slash}FSMC_A23{slash}ETH_MII_TXD3-Pad1)") (class "Default")
      (node (ref "U1") (pin "1") (pinfunction "PE2/TRACECLK/FSMC_A23/ETH_MII_TXD3_1") (pintype "passive"))
    )
    (net (code "102") (name "unconnected-(U1-PE3{slash}TRACED0{slash}FSMC_A19-Pad2)") (class "Default")
      (node (ref "U1") (pin "2") (pinfunction "PE3/TRACED0/FSMC_A19_2") (pintype "passive"))
    )
    (net (code "103") (name "unconnected-(U1-PE4{slash}TRACED1{slash}FSMC_A20{slash}DCMI_D4-Pad3)") (class "Default")
      (node (ref "U1") (pin "3") (pinfunction "PE4/TRACED1/FSMC_A20/DCMI_D4_3") (pintype "passive"))
    )
    (net (code "104") (name "unconnected-(U1-PE5{slash}TRACED2{slash}FSMC_A21{slash}TIM9_CH1{slash}DCMI_D6-Pad4)") (class "Default")
      (node (ref "U1") (pin "4") (pinfunction "PE5/TRACED2/FSMC_A21/TIM9_CH1/DCMI_D6_4") (pintype "passive"))
    )
    (net (code "105") (name "unconnected-(U1-PE6{slash}TRACED3{slash}FSMC_A22{slash}TIM9_CH2{slash}DCMI_D7-Pad5)") (class "Default")
      (node (ref "U1") (pin "5") (pinfunction "PE6/TRACED3/FSMC_A22/TIM9_CH2/DCMI_D7_5") (pintype "passive"))
    )
    (net (code "106") (name "unconnected-(U1-PE7{slash}FSMC_D4{slash}TIM1_ETR-Pad58)") (class "Default")
      (node (ref "U1") (pin "58") (pinfunction "PE7/FSMC_D4/TIM1_ETR_58") (pintype "passive"))
    )
    (net (code "107") (name "unconnected-(U1-PE8{slash}FSMC_D5{slash}TIM1_CH1N-Pad59)") (class "Default")
      (node (ref "U1") (pin "59") (pinfunction "PE8/FSMC_D5/TIM1_CH1N_59") (pintype "passive"))
    )
    (net (code "108") (name "unconnected-(U1-PE10{slash}FSMC_D7{slash}TIM1_CH2N-Pad63)") (class "Default")
      (node (ref "U1") (pin "63") (pinfunction "PE10/FSMC_D7/TIM1_CH2N_63") (pintype "passive"))
    )
    (net (code "109") (name "unconnected-(U1-PE11{slash}FSMC_D8{slash}TIM1_CH2-Pad64)") (class "Default")
      (node (ref "U1") (pin "64") (pinfunction "PE11/FSMC_D8/TIM1_CH2_64") (pintype "passive"))
    )
    (net (code "110") (name "unconnected-(U1-PE12{slash}FSMC_D9{slash}TIM1_CH3N-Pad65)") (class "Default")
      (node (ref "U1") (pin "65") (pinfunction "PE12/FSMC_D9/TIM1_CH3N_65") (pintype "passive"))
    )
    (net (code "111") (name "unconnected-(U1-PE13{slash}FSMC_D10{slash}TIM1_CH3-Pad66)") (class "Default")
      (node (ref "U1") (pin "66") (pinfunction "PE13/FSMC_D10/TIM1_CH3_66") (pintype "passive"))
    )
    (net (code "112") (name "unconnected-(U1-PE14{slash}FSMC_D11{slash}TIM1_CH4-Pad67)") (class "Default")
      (node (ref "U1") (pin "67") (pinfunction "PE14/FSMC_D11/TIM1_CH4_67") (pintype "passive"))
    )
    (net (code "113") (name "unconnected-(U1-PE15{slash}FSMC_D12{slash}TIM1_BKIN-Pad68)") (class "Default")
      (node (ref "U1") (pin "68") (pinfunction "PE15/FSMC_D12/TIM1_BKIN_68") (pintype "passive"))
    )
    (net (code "114") (name "unconnected-(U1-PF0{slash}FSMC_A0{slash}I2C2_SDA-Pad10)") (class "Default")
      (node (ref "U1") (pin "10") (pinfunction "PF0/FSMC_A0/I2C2_SDA_10") (pintype "passive"))
    )
    (net (code "115") (name "unconnected-(U1-PF1{slash}FSMC_A1{slash}I2C2_SCL-Pad11)") (class "Default")
      (node (ref "U1") (pin "11") (pinfunction "PF1/FSMC_A1/I2C2_SCL_11") (pintype "passive"))
    )
    (net (code "116") (name "unconnected-(U1-PF2{slash}FSMC_A2{slash}I2C2_SMBA-Pad12)") (class "Default")
      (node (ref "U1") (pin "12") (pinfunction "PF2/FSMC_A2/I2C2_SMBA_12") (pintype "passive"))
    )
    (net (code "117") (name "unconnected-(U1-PF3{slash}FSMC_A3{slash}ADC3_IN9-Pad13)") (class "Default")
      (node (ref "U1") (pin "13") (pinfunction "PF3/FSMC_A3/ADC3_IN9_13") (pintype "passive"))
    )
    (net (code "118") (name "unconnected-(U1-PF4{slash}FSMC_A4{slash}ADC3_IN14-Pad14)") (class "Default")
      (node (ref "U1") (pin "14") (pinfunction "PF4/FSMC_A4/ADC3_IN14_14") (pintype "passive"))
    )
    (net (code "119") (name "unconnected-(U1-PF5{slash}FSMC_A5{slash}ADC3_IN15-Pad15)") (class "Default")
      (node (ref "U1") (pin "15") (pinfunction "PF5/FSMC_A5/ADC3_IN15_15") (pintype "passive"))
    )
    (net (code "120") (name "unconnected-(U1-PF6{slash}TIM10_CH1{slash}FSMC_NIORD{slash}ADC3_IN4-Pad18)") (class "Default")
      (node (ref "U1") (pin "18") (pinfunction "PF6/TIM10_CH1/FSMC_NIORD/ADC3_IN4_18") (pintype "passive"))
    )
    (net (code "121") (name "unconnected-(U1-PF7{slash}TIM11_CH1{slash}FSMC_NREG{slash}ADC3_IN5-Pad19)") (class "Default")
      (node (ref "U1") (pin "19") (pinfunction "PF7/TIM11_CH1/FSMC_NREG/ADC3_IN5_19") (pintype "passive"))
    )
    (net (code "122") (name "unconnected-(U1-PF8{slash}TIM13_CH1{slash}FSMC_NIOWR{slash}ADC3_IN6-Pad20)") (class "Default")
      (node (ref "U1") (pin "20") (pinfunction "PF8/TIM13_CH1/FSMC_NIOWR/ADC3_IN6_20") (pintype "passive"))
    )
    (net (code "123") (name "unconnected-(U1-PF9{slash}TIM14_CH1{slash}FSMC_CD{slash}ADC3_IN7-Pad21)") (class "Default")
      (node (ref "U1") (pin "21") (pinfunction "PF9/TIM14_CH1/FSMC_CD/ADC3_IN7_21") (pintype "passive"))
    )
    (net (code "124") (name "unconnected-(U1-PF10{slash}FSMC_INTR{slash}ADC3_IN8-Pad22)") (class "Default")
      (node (ref "U1") (pin "22") (pinfunction "PF10/FSMC_INTR/ADC3_IN8_22") (pintype "passive"))
    )
    (net (code "125") (name "unconnected-(U1-PF11{slash}DCMI_D12-Pad49)") (class "Default")
      (node (ref "U1") (pin "49") (pinfunction "PF11/DCMI_D12_49") (pintype "passive"))
    )
    (net (code "126") (name "unconnected-(U1-PF12{slash}FSMC_A6-Pad50)") (class "Default")
      (node (ref "U1") (pin "50") (pinfunction "PF12/FSMC_A6_50") (pintype "passive"))
    )
    (net (code "127") (name "unconnected-(U1-PF13{slash}FSMC_A7-Pad53)") (class "Default")
      (node (ref "U1") (pin "53") (pinfunction "PF13/FSMC_A7_53") (pintype "passive"))
    )
    (net (code "128") (name "unconnected-(U1-PF14{slash}FSMC_A8-Pad54)") (class "Default")
      (node (ref "U1") (pin "54") (pinfunction "PF14/FSMC_A8_54") (pintype "passive"))
    )
    (net (code "129") (name "unconnected-(U1-PF15{slash}FSMC_A9-Pad55)") (class "Default")
      (node (ref "U1") (pin "55") (pinfunction "PF15/FSMC_A9_55") (pintype "passive"))
    )
    (net (code "130") (name "unconnected-(U1-PG0{slash}FSMC_A10-Pad56)") (class "Default")
      (node (ref "U1") (pin "56") (pinfunction "PG0/FSMC_A10_56") (pintype "passive"))
    )
    (net (code "131") (name "unconnected-(U1-PG1{slash}FSMC_A11-Pad57)") (class "Default")
      (node (ref "U1") (pin "57") (pinfunction "PG1/FSMC_A11_57") (pintype "passive"))
    )
    (net (code "132") (name "unconnected-(U1-PG2{slash}FSMC_A12-Pad87)") (class "Default")
      (node (ref "U1") (pin "87") (pinfunction "PG2/FSMC_A12_87") (pintype "passive"))
    )
    (net (code "133") (name "unconnected-(U1-PG3{slash}FSMC_A13-Pad88)") (class "Default")
      (node (ref "U1") (pin "88") (pinfunction "PG3/FSMC_A13_88") (pintype "passive"))
    )
    (net (code "134") (name "unconnected-(U1-PG4{slash}FSMC_A14-Pad89)") (class "Default")
      (node (ref "U1") (pin "89") (pinfunction "PG4/FSMC_A14_89") (pintype "passive"))
    )
    (net (code "135") (name "unconnected-(U1-PG5{slash}FSMC_A15-Pad90)") (class "Default")
      (node (ref "U1") (pin "90") (pinfunction "PG5/FSMC_A15_90") (pintype "passive"))
    )
    (net (code "136") (name "unconnected-(U1-PG6{slash}FSMC_INT2-Pad91)") (class "Default")
      (node (ref "U1") (pin "91") (pinfunction "PG6/FSMC_INT2_91") (pintype "passive"))
    )
    (net (code "137") (name "unconnected-(U1-PG7{slash}FSMC_INT3{slash}U6_CK-Pad92)") (class "Default")
      (node (ref "U1") (pin "92") (pinfunction "PG7/FSMC_INT3/U6_CK_92") (pintype "passive"))
    )
    (net (code "138") (name "unconnected-(U1-PG8{slash}U6_RTS{slash}ETH_PPS_OUT-Pad93)") (class "Default")
      (node (ref "U1") (pin "93") (pinfunction "PG8/U6_RTS/ETH_PPS_OUT_93") (pintype "passive"))
    )
    (net (code "139") (name "unconnected-(U1-PG9{slash}FSMC_NE2{slash}FSMC_NCE3{slash}U6_RX-Pad124)") (class "Default")
      (node (ref "U1") (pin "124") (pinfunction "PG9/FSMC_NE2/FSMC_NCE3/U6_RX_124") (pintype "passive"))
    )
    (net (code "140") (name "unconnected-(U1-PG10{slash}FSMC_NCE4_1{slash}FSMC_NE3-Pad125)") (class "Default")
      (node (ref "U1") (pin "125") (pinfunction "PG10/FSMC_NCE4_1/FSMC_NE3_125") (pintype "passive"))
    )
    (net (code "141") (name "unconnected-(U1-PG11{slash}FSMC_NCE4_2{slash}ETH_MII_TX_EN{slash}ETH_RMII_TX_EN-Pad126)") (class "Default")
      (node (ref "U1") (pin "126") (pinfunction "PG11/FSMC_NCE4_2/ETH_MII_TX_EN/ETH_RMII_TX_EN_126") (pintype "passive"))
    )
    (net (code "142") (name "unconnected-(U1-PG12{slash}FSMC_NE4{slash}U6_RTS-Pad127)") (class "Default")
      (node (ref "U1") (pin "127") (pinfunction "PG12/FSMC_NE4/U6_RTS_127") (pintype "passive"))
    )
    (net (code "143") (name "unconnected-(U1-PG13{slash}FSMC_A24{slash}U6_CTS{slash}ETH_MII_TXD0{slash}ETH_RMII_TXD0-Pad128)") (class "Default")
      (node (ref "U1") (pin "128") (pinfunction "PG13/FSMC_A24/U6_CTS/ETH_MII_TXD0/ETH_RMII_TXD0_128") (pintype "passive"))
    )
    (net (code "144") (name "unconnected-(U1-PG14{slash}FSMC_A25{slash}U6_TX{slash}ETH_MII_TXD1{slash}ETH_RMII_TXD1-Pad129)") (class "Default")
      (node (ref "U1") (pin "129") (pinfunction "PG14/FSMC_A25/U6_TX/ETH_MII_TXD1/ETH_RMII_TXD1_129") (pintype "passive"))
    )
    (net (code "145") (name "unconnected-(U1-PG15{slash}U6_CTS{slash}DCMI_D13-Pad132)") (class "Default")
      (node (ref "U1") (pin "132") (pinfunction "PG15/U6_CTS/DCMI_D13_132") (pintype "passive"))
    )
    (net (code "146") (name "unconnected-(U3-n.c.-Pad5)") (class "Default")
      (node (ref "U3") (pin "5") (pinfunction "n.c._5") (pintype "passive+no_connect"))
    )
    (net (code "147") (name "unconnected-(U4-CTS#-Pad9)") (class "Default")
      (node (ref "U4") (pin "9") (pinfunction "CTS#_9") (pintype "passive"))
    )
    (net (code "148") (name "unconnected-(U4-DCD#-Pad13)") (class "Default")
      (node (ref "U4") (pin "13") (pinfunction "DCD#_13") (pintype "passive"))
    )
    (net (code "149") (name "unconnected-(U4-DSR#-Pad15)") (class "Default")
      (node (ref "U4") (pin "15") (pinfunction "DSR#_15") (pintype "passive"))
    )
    (net (code "150") (name "unconnected-(U4-DTR#-Pad12)") (class "Default")
      (node (ref "U4") (pin "12") (pinfunction "DTR#_12") (pintype "passive"))
    )
    (net (code "151") (name "unconnected-(U4-R232-Pad10)") (class "Default")
      (node (ref "U4") (pin "10") (pinfunction "R232_10") (pintype "passive"))
    )
    (net (code "152") (name "unconnected-(U4-RI#-Pad14)") (class "Default")
      (node (ref "U4") (pin "14") (pinfunction "RI#_14") (pintype "passive"))
    )
    (net (code "153") (name "unconnected-(U4-RTS#-Pad11)") (class "Default")
      (node (ref "U4") (pin "11") (pinfunction "RTS#_11") (pintype "passive"))
    )
    (net (code "154") (name "unconnected-(USB_SLAVE-NC-Pad4)") (class "Default")
      (node (ref "USB_SLAVE") (pin "4") (pinfunction "NC_4") (pintype "passive"))
    )
    (net (code "155") (name "unconnected-(右编码器-Pad1)") (class "Default")
      (node (ref "右编码器") (pin "1") (pinfunction "1_1") (pintype "passive"))
    )
    (net (code "156") (name "unconnected-(右编码器-Pad2)") (class "Default")
      (node (ref "右编码器") (pin "2") (pinfunction "2_2") (pintype "passive"))
    )
    (net (code "157") (name "unconnected-(右编码器-Pad3)") (class "Default")
      (node (ref "右编码器") (pin "3") (pinfunction "3_3") (pintype "passive"))
    )
    (net (code "158") (name "unconnected-(右编码器-Pad4)") (class "Default")
      (node (ref "右编码器") (pin "4") (pinfunction "4_4") (pintype "passive"))
    )
    (net (code "159") (name "unconnected-(右编码器-Pad5)") (class "Default")
      (node (ref "右编码器") (pin "5") (pinfunction "5_5") (pintype "passive"))
    )
    (net (code "160") (name "unconnected-(右编码器-Pad6)") (class "Default")
      (node (ref "右编码器") (pin "6") (pinfunction "6_6") (pintype "passive"))
    )
    (net (code "161") (name "unconnected-(右编码器-Pad7)") (class "Default")
      (node (ref "右编码器") (pin "7") (pinfunction "7_7") (pintype "passive"))
    )
    (net (code "162") (name "unconnected-(右编码器-Pad8)") (class "Default")
      (node (ref "右编码器") (pin "8") (pinfunction "8_8") (pintype "passive"))
    )
    (net (code "163") (name "unconnected-(右编码器-Pad9)") (class "Default")
      (node (ref "右编码器") (pin "9") (pinfunction "9_9") (pintype "passive"))
    )
    (net (code "164") (name "unconnected-(右编码器-Pad10)") (class "Default")
      (node (ref "右编码器") (pin "10") (pinfunction "10_10") (pintype "passive"))
    )
    (net (code "165") (name "unconnected-(右编码器-Pad11)") (class "Default")
      (node (ref "右编码器") (pin "11") (pinfunction "11_11") (pintype "passive"))
    )
    (net (code "166") (name "unconnected-(右编码器-Pad12)") (class "Default")
      (node (ref "右编码器") (pin "12") (pinfunction "12_12") (pintype "passive"))
    )
    (net (code "167") (name "unconnected-(左编码器-Pad1)") (class "Default")
      (node (ref "左编码器") (pin "1") (pinfunction "1_1") (pintype "passive"))
    )
    (net (code "168") (name "unconnected-(左编码器-Pad2)") (class "Default")
      (node (ref "左编码器") (pin "2") (pinfunction "2_2") (pintype "passive"))
    )
    (net (code "169") (name "unconnected-(左编码器-Pad3)") (class "Default")
      (node (ref "左编码器") (pin "3") (pinfunction "3_3") (pintype "passive"))
    )
    (net (code "170") (name "unconnected-(左编码器-Pad4)") (class "Default")
      (node (ref "左编码器") (pin "4") (pinfunction "4_4") (pintype "passive"))
    )
    (net (code "171") (name "unconnected-(左编码器-Pad5)") (class "Default")
      (node (ref "左编码器") (pin "5") (pinfunction "5_5") (pintype "passive"))
    )
    (net (code "172") (name "unconnected-(左编码器-Pad6)") (class "Default")
      (node (ref "左编码器") (pin "6") (pinfunction "6_6") (pintype "passive"))
    )
    (net (code "173") (name "unconnected-(左编码器-Pad7)") (class "Default")
      (node (ref "左编码器") (pin "7") (pinfunction "7_7") (pintype "passive"))
    )
    (net (code "174") (name "unconnected-(左编码器-Pad8)") (class "Default")
      (node (ref "左编码器") (pin "8") (pinfunction "8_8") (pintype "passive"))
    )
    (net (code "175") (name "unconnected-(左编码器-Pad9)") (class "Default")
      (node (ref "左编码器") (pin "9") (pinfunction "9_9") (pintype "passive"))
    )
    (net (code "176") (name "unconnected-(左编码器-Pad10)") (class "Default")
      (node (ref "左编码器") (pin "10") (pinfunction "10_10") (pintype "passive"))
    )
    (net (code "177") (name "unconnected-(左编码器-Pad11)") (class "Default")
      (node (ref "左编码器") (pin "11") (pinfunction "11_11") (pintype "passive"))
    )
    (net (code "178") (name "unconnected-(左编码器-Pad12)") (class "Default")
      (node (ref "左编码器") (pin "12") (pinfunction "12_12") (pintype "passive"))
    )
  )
)
